# LEDCube.net
KiCad netlist of a schematic drawn in EAGLE
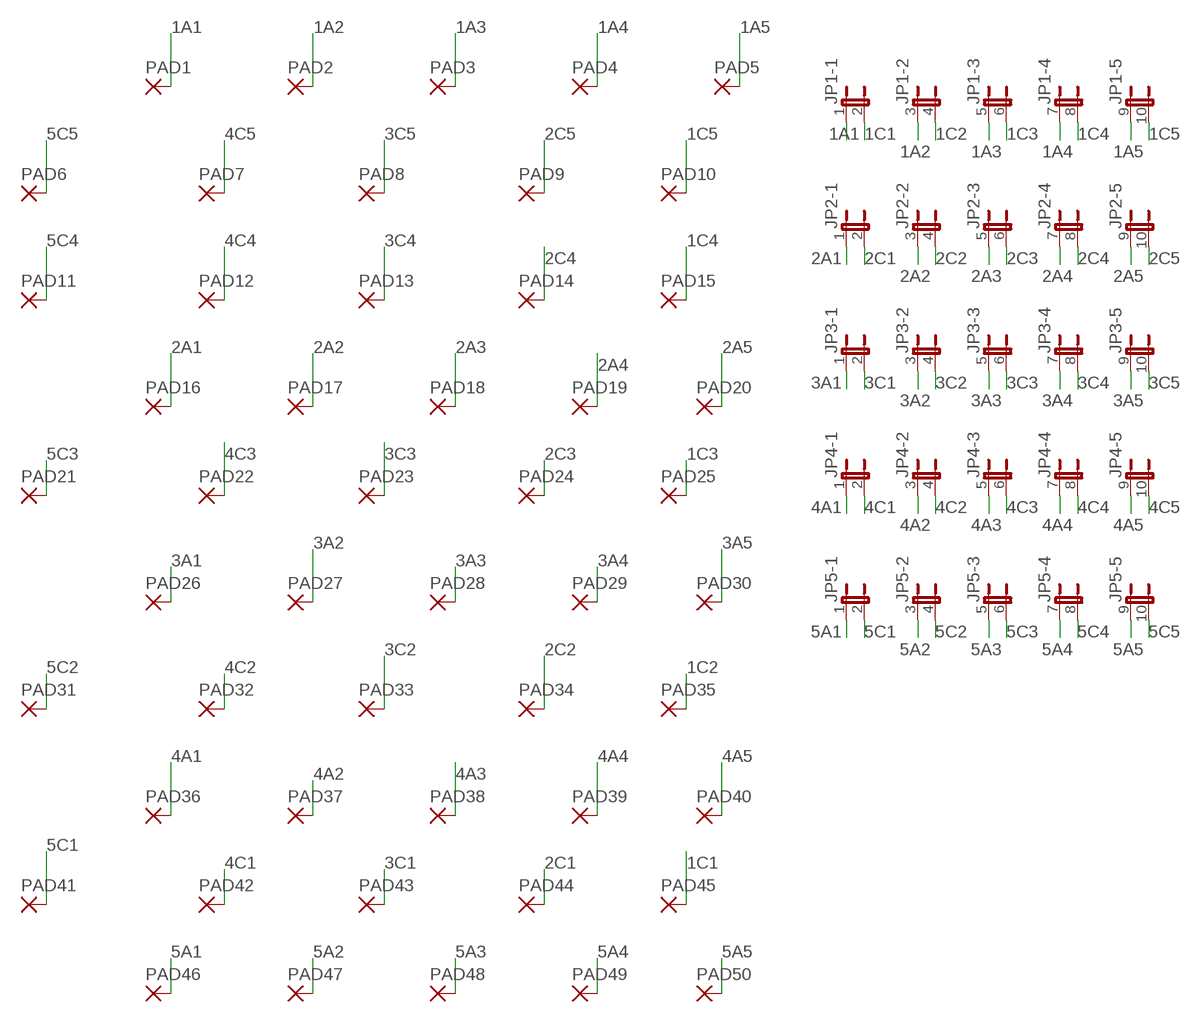
[diagram p0: schematic, sheet 1]

(export (version "E")
  (design (tool "Eeschema 10.0.6"))
  (components
    (comp (ref "JP1")
      (value "JP5QE")
      (footprint "eagle-import:JP5Q")
      (libsource (lib "eagle-import") (part "JP5QE"))
    )
    (comp (ref "JP2")
      (value "JP5QE")
      (footprint "eagle-import:JP5Q")
      (libsource (lib "eagle-import") (part "JP5QE"))
    )
    (comp (ref "JP3")
      (value "JP5QE")
      (footprint "eagle-import:JP5Q")
      (libsource (lib "eagle-import") (part "JP5QE"))
    )
    (comp (ref "JP4")
      (value "JP5QE")
      (footprint "eagle-import:JP5Q")
      (libsource (lib "eagle-import") (part "JP5QE"))
    )
    (comp (ref "JP5")
      (value "JP5QE")
      (footprint "eagle-import:JP5Q")
      (libsource (lib "eagle-import") (part "JP5QE"))
    )
    (comp (ref "PAD1")
      (value "2,54/1,1")
      (footprint "eagle-import:2,54_1,1")
      (libsource (lib "eagle-import") (part "2,54/1,1"))
    )
    (comp (ref "PAD2")
      (value "2,54/1,1")
      (footprint "eagle-import:2,54_1,1")
      (libsource (lib "eagle-import") (part "2,54/1,1"))
    )
    (comp (ref "PAD3")
      (value "2,54/1,1")
      (footprint "eagle-import:2,54_1,1")
      (libsource (lib "eagle-import") (part "2,54/1,1"))
    )
    (comp (ref "PAD4")
      (value "2,54/1,1")
      (footprint "eagle-import:2,54_1,1")
      (libsource (lib "eagle-import") (part "2,54/1,1"))
    )
    (comp (ref "PAD5")
      (value "2,54/1,1")
      (footprint "eagle-import:2,54_1,1")
      (libsource (lib "eagle-import") (part "2,54/1,1"))
    )
    (comp (ref "PAD6")
      (value "2,54/1,1")
      (footprint "eagle-import:2,54_1,1")
      (libsource (lib "eagle-import") (part "2,54/1,1"))
    )
    (comp (ref "PAD7")
      (value "2,54/1,1")
      (footprint "eagle-import:2,54_1,1")
      (libsource (lib "eagle-import") (part "2,54/1,1"))
    )
    (comp (ref "PAD8")
      (value "2,54/1,1")
      (footprint "eagle-import:2,54_1,1")
      (libsource (lib "eagle-import") (part "2,54/1,1"))
    )
    (comp (ref "PAD9")
      (value "2,54/1,1")
      (footprint "eagle-import:2,54_1,1")
      (libsource (lib "eagle-import") (part "2,54/1,1"))
    )
    (comp (ref "PAD10")
      (value "2,54/1,1")
      (footprint "eagle-import:2,54_1,1")
      (libsource (lib "eagle-import") (part "2,54/1,1"))
    )
    (comp (ref "PAD11")
      (value "2,54/1,1")
      (footprint "eagle-import:2,54_1,1")
      (libsource (lib "eagle-import") (part "2,54/1,1"))
    )
    (comp (ref "PAD12")
      (value "2,54/1,1")
      (footprint "eagle-import:2,54_1,1")
      (libsource (lib "eagle-import") (part "2,54/1,1"))
    )
    (comp (ref "PAD13")
      (value "2,54/1,1")
      (footprint "eagle-import:2,54_1,1")
      (libsource (lib "eagle-import") (part "2,54/1,1"))
    )
    (comp (ref "PAD14")
      (value "2,54/1,1")
      (footprint "eagle-import:2,54_1,1")
      (libsource (lib "eagle-import") (part "2,54/1,1"))
    )
    (comp (ref "PAD15")
      (value "2,54/1,1")
      (footprint "eagle-import:2,54_1,1")
      (libsource (lib "eagle-import") (part "2,54/1,1"))
    )
    (comp (ref "PAD16")
      (value "2,54/1,1")
      (footprint "eagle-import:2,54_1,1")
      (libsource (lib "eagle-import") (part "2,54/1,1"))
    )
    (comp (ref "PAD17")
      (value "2,54/1,1")
      (footprint "eagle-import:2,54_1,1")
      (libsource (lib "eagle-import") (part "2,54/1,1"))
    )
    (comp (ref "PAD18")
      (value "2,54/1,1")
      (footprint "eagle-import:2,54_1,1")
      (libsource (lib "eagle-import") (part "2,54/1,1"))
    )
    (comp (ref "PAD19")
      (value "2,54/1,1")
      (footprint "eagle-import:2,54_1,1")
      (libsource (lib "eagle-import") (part "2,54/1,1"))
    )
    (comp (ref "PAD20")
      (value "2,54/1,1")
      (footprint "eagle-import:2,54_1,1")
      (libsource (lib "eagle-import") (part "2,54/1,1"))
    )
    (comp (ref "PAD21")
      (value "2,54/1,1")
      (footprint "eagle-import:2,54_1,1")
      (libsource (lib "eagle-import") (part "2,54/1,1"))
    )
    (comp (ref "PAD22")
      (value "2,54/1,1")
      (footprint "eagle-import:2,54_1,1")
      (libsource (lib "eagle-import") (part "2,54/1,1"))
    )
    (comp (ref "PAD23")
      (value "2,54/1,1")
      (footprint "eagle-import:2,54_1,1")
      (libsource (lib "eagle-import") (part "2,54/1,1"))
    )
    (comp (ref "PAD24")
      (value "2,54/1,1")
      (footprint "eagle-import:2,54_1,1")
      (libsource (lib "eagle-import") (part "2,54/1,1"))
    )
    (comp (ref "PAD25")
      (value "2,54/1,1")
      (footprint "eagle-import:2,54_1,1")
      (libsource (lib "eagle-import") (part "2,54/1,1"))
    )
    (comp (ref "PAD26")
      (value "2,54/1,1")
      (footprint "eagle-import:2,54_1,1")
      (libsource (lib "eagle-import") (part "2,54/1,1"))
    )
    (comp (ref "PAD27")
      (value "2,54/1,1")
      (footprint "eagle-import:2,54_1,1")
      (libsource (lib "eagle-import") (part "2,54/1,1"))
    )
    (comp (ref "PAD28")
      (value "2,54/1,1")
      (footprint "eagle-import:2,54_1,1")
      (libsource (lib "eagle-import") (part "2,54/1,1"))
    )
    (comp (ref "PAD29")
      (value "2,54/1,1")
      (footprint "eagle-import:2,54_1,1")
      (libsource (lib "eagle-import") (part "2,54/1,1"))
    )
    (comp (ref "PAD30")
      (value "2,54/1,1")
      (footprint "eagle-import:2,54_1,1")
      (libsource (lib "eagle-import") (part "2,54/1,1"))
    )
    (comp (ref "PAD31")
      (value "2,54/1,1")
      (footprint "eagle-import:2,54_1,1")
      (libsource (lib "eagle-import") (part "2,54/1,1"))
    )
    (comp (ref "PAD32")
      (value "2,54/1,1")
      (footprint "eagle-import:2,54_1,1")
      (libsource (lib "eagle-import") (part "2,54/1,1"))
    )
    (comp (ref "PAD33")
      (value "2,54/1,1")
      (footprint "eagle-import:2,54_1,1")
      (libsource (lib "eagle-import") (part "2,54/1,1"))
    )
    (comp (ref "PAD34")
      (value "2,54/1,1")
      (footprint "eagle-import:2,54_1,1")
      (libsource (lib "eagle-import") (part "2,54/1,1"))
    )
    (comp (ref "PAD35")
      (value "2,54/1,1")
      (footprint "eagle-import:2,54_1,1")
      (libsource (lib "eagle-import") (part "2,54/1,1"))
    )
    (comp (ref "PAD36")
      (value "2,54/1,1")
      (footprint "eagle-import:2,54_1,1")
      (libsource (lib "eagle-import") (part "2,54/1,1"))
    )
    (comp (ref "PAD37")
      (value "2,54/1,1")
      (footprint "eagle-import:2,54_1,1")
      (libsource (lib "eagle-import") (part "2,54/1,1"))
    )
    (comp (ref "PAD38")
      (value "2,54/1,1")
      (footprint "eagle-import:2,54_1,1")
      (libsource (lib "eagle-import") (part "2,54/1,1"))
    )
    (comp (ref "PAD39")
      (value "2,54/1,1")
      (footprint "eagle-import:2,54_1,1")
      (libsource (lib "eagle-import") (part "2,54/1,1"))
    )
    (comp (ref "PAD40")
      (value "2,54/1,1")
      (footprint "eagle-import:2,54_1,1")
      (libsource (lib "eagle-import") (part "2,54/1,1"))
    )
    (comp (ref "PAD41")
      (value "2,54/1,1")
      (footprint "eagle-import:2,54_1,1")
      (libsource (lib "eagle-import") (part "2,54/1,1"))
    )
    (comp (ref "PAD42")
      (value "2,54/1,1")
      (footprint "eagle-import:2,54_1,1")
      (libsource (lib "eagle-import") (part "2,54/1,1"))
    )
    (comp (ref "PAD43")
      (value "2,54/1,1")
      (footprint "eagle-import:2,54_1,1")
      (libsource (lib "eagle-import") (part "2,54/1,1"))
    )
    (comp (ref "PAD44")
      (value "2,54/1,1")
      (footprint "eagle-import:2,54_1,1")
      (libsource (lib "eagle-import") (part "2,54/1,1"))
    )
    (comp (ref "PAD45")
      (value "2,54/1,1")
      (footprint "eagle-import:2,54_1,1")
      (libsource (lib "eagle-import") (part "2,54/1,1"))
    )
    (comp (ref "PAD46")
      (value "2,54/1,1")
      (footprint "eagle-import:2,54_1,1")
      (libsource (lib "eagle-import") (part "2,54/1,1"))
    )
    (comp (ref "PAD47")
      (value "2,54/1,1")
      (footprint "eagle-import:2,54_1,1")
      (libsource (lib "eagle-import") (part "2,54/1,1"))
    )
    (comp (ref "PAD48")
      (value "2,54/1,1")
      (footprint "eagle-import:2,54_1,1")
      (libsource (lib "eagle-import") (part "2,54/1,1"))
    )
    (comp (ref "PAD49")
      (value "2,54/1,1")
      (footprint "eagle-import:2,54_1,1")
      (libsource (lib "eagle-import") (part "2,54/1,1"))
    )
    (comp (ref "PAD50")
      (value "2,54/1,1")
      (footprint "eagle-import:2,54_1,1")
      (libsource (lib "eagle-import") (part "2,54/1,1"))
    )
  )
  (nets
    (net (code "1") (name "/1A1") (class "Default")
      (node (ref "JP1") (pin "1") (pinfunction "1_1") (pintype "passive"))
      (node (ref "PAD1") (pin "1") (pinfunction "P_1") (pintype "passive"))
    )
    (net (code "2") (name "/1A2") (class "Default")
      (node (ref "JP1") (pin "3") (pinfunction "1_3") (pintype "passive"))
      (node (ref "PAD2") (pin "1") (pinfunction "P_1") (pintype "passive"))
    )
    (net (code "3") (name "/1A3") (class "Default")
      (node (ref "JP1") (pin "5") (pinfunction "1_5") (pintype "passive"))
      (node (ref "PAD3") (pin "1") (pinfunction "P_1") (pintype "passive"))
    )
    (net (code "4") (name "/1A4") (class "Default")
      (node (ref "JP1") (pin "7") (pinfunction "1_7") (pintype "passive"))
      (node (ref "PAD4") (pin "1") (pinfunction "P_1") (pintype "passive"))
    )
    (net (code "5") (name "/1A5") (class "Default")
      (node (ref "JP1") (pin "9") (pinfunction "1_9") (pintype "passive"))
      (node (ref "PAD5") (pin "1") (pinfunction "P_1") (pintype "passive"))
    )
    (net (code "6") (name "/1C1") (class "Default")
      (node (ref "JP1") (pin "2") (pinfunction "2_2") (pintype "passive"))
      (node (ref "PAD45") (pin "1") (pinfunction "P_1") (pintype "passive"))
    )
    (net (code "7") (name "/1C2") (class "Default")
      (node (ref "JP1") (pin "4") (pinfunction "2_4") (pintype "passive"))
      (node (ref "PAD35") (pin "1") (pinfunction "P_1") (pintype "passive"))
    )
    (net (code "8") (name "/1C3") (class "Default")
      (node (ref "JP1") (pin "6") (pinfunction "2_6") (pintype "passive"))
      (node (ref "PAD25") (pin "1") (pinfunction "P_1") (pintype "passive"))
    )
    (net (code "9") (name "/1C4") (class "Default")
      (node (ref "JP1") (pin "8") (pinfunction "2_8") (pintype "passive"))
      (node (ref "PAD15") (pin "1") (pinfunction "P_1") (pintype "passive"))
    )
    (net (code "10") (name "/1C5") (class "Default")
      (node (ref "JP1") (pin "10") (pinfunction "2_10") (pintype "passive"))
      (node (ref "PAD10") (pin "1") (pinfunction "P_1") (pintype "passive"))
    )
    (net (code "11") (name "/2A1") (class "Default")
      (node (ref "JP2") (pin "1") (pinfunction "1_1") (pintype "passive"))
      (node (ref "PAD16") (pin "1") (pinfunction "P_1") (pintype "passive"))
    )
    (net (code "12") (name "/2A2") (class "Default")
      (node (ref "JP2") (pin "3") (pinfunction "1_3") (pintype "passive"))
      (node (ref "PAD17") (pin "1") (pinfunction "P_1") (pintype "passive"))
    )
    (net (code "13") (name "/2A3") (class "Default")
      (node (ref "JP2") (pin "5") (pinfunction "1_5") (pintype "passive"))
      (node (ref "PAD18") (pin "1") (pinfunction "P_1") (pintype "passive"))
    )
    (net (code "14") (name "/2A4") (class "Default")
      (node (ref "JP2") (pin "7") (pinfunction "1_7") (pintype "passive"))
      (node (ref "PAD19") (pin "1") (pinfunction "P_1") (pintype "passive"))
    )
    (net (code "15") (name "/2A5") (class "Default")
      (node (ref "JP2") (pin "9") (pinfunction "1_9") (pintype "passive"))
      (node (ref "PAD20") (pin "1") (pinfunction "P_1") (pintype "passive"))
    )
    (net (code "16") (name "/2C1") (class "Default")
      (node (ref "JP2") (pin "2") (pinfunction "2_2") (pintype "passive"))
      (node (ref "PAD44") (pin "1") (pinfunction "P_1") (pintype "passive"))
    )
    (net (code "17") (name "/2C2") (class "Default")
      (node (ref "JP2") (pin "4") (pinfunction "2_4") (pintype "passive"))
      (node (ref "PAD34") (pin "1") (pinfunction "P_1") (pintype "passive"))
    )
    (net (code "18") (name "/2C3") (class "Default")
      (node (ref "JP2") (pin "6") (pinfunction "2_6") (pintype "passive"))
      (node (ref "PAD24") (pin "1") (pinfunction "P_1") (pintype "passive"))
    )
    (net (code "19") (name "/2C4") (class "Default")
      (node (ref "JP2") (pin "8") (pinfunction "2_8") (pintype "passive"))
      (node (ref "PAD14") (pin "1") (pinfunction "P_1") (pintype "passive"))
    )
    (net (code "20") (name "/2C5") (class "Default")
      (node (ref "JP2") (pin "10") (pinfunction "2_10") (pintype "passive"))
      (node (ref "PAD9") (pin "1") (pinfunction "P_1") (pintype "passive"))
    )
    (net (code "21") (name "/3A1") (class "Default")
      (node (ref "JP3") (pin "1") (pinfunction "1_1") (pintype "passive"))
      (node (ref "PAD26") (pin "1") (pinfunction "P_1") (pintype "passive"))
    )
    (net (code "22") (name "/3A2") (class "Default")
      (node (ref "JP3") (pin "3") (pinfunction "1_3") (pintype "passive"))
      (node (ref "PAD27") (pin "1") (pinfunction "P_1") (pintype "passive"))
    )
    (net (code "23") (name "/3A3") (class "Default")
      (node (ref "JP3") (pin "5") (pinfunction "1_5") (pintype "passive"))
      (node (ref "PAD28") (pin "1") (pinfunction "P_1") (pintype "passive"))
    )
    (net (code "24") (name "/3A4") (class "Default")
      (node (ref "JP3") (pin "7") (pinfunction "1_7") (pintype "passive"))
      (node (ref "PAD29") (pin "1") (pinfunction "P_1") (pintype "passive"))
    )
    (net (code "25") (name "/3A5") (class "Default")
      (node (ref "JP3") (pin "9") (pinfunction "1_9") (pintype "passive"))
      (node (ref "PAD30") (pin "1") (pinfunction "P_1") (pintype "passive"))
    )
    (net (code "26") (name "/3C1") (class "Default")
      (node (ref "JP3") (pin "2") (pinfunction "2_2") (pintype "passive"))
      (node (ref "PAD43") (pin "1") (pinfunction "P_1") (pintype "passive"))
    )
    (net (code "27") (name "/3C2") (class "Default")
      (node (ref "JP3") (pin "4") (pinfunction "2_4") (pintype "passive"))
      (node (ref "PAD33") (pin "1") (pinfunction "P_1") (pintype "passive"))
    )
    (net (code "28") (name "/3C3") (class "Default")
      (node (ref "JP3") (pin "6") (pinfunction "2_6") (pintype "passive"))
      (node (ref "PAD23") (pin "1") (pinfunction "P_1") (pintype "passive"))
    )
    (net (code "29") (name "/3C4") (class "Default")
      (node (ref "JP3") (pin "8") (pinfunction "2_8") (pintype "passive"))
      (node (ref "PAD13") (pin "1") (pinfunction "P_1") (pintype "passive"))
    )
    (net (code "30") (name "/3C5") (class "Default")
      (node (ref "JP3") (pin "10") (pinfunction "2_10") (pintype "passive"))
      (node (ref "PAD8") (pin "1") (pinfunction "P_1") (pintype "passive"))
    )
    (net (code "31") (name "/4A1") (class "Default")
      (node (ref "JP4") (pin "1") (pinfunction "1_1") (pintype "passive"))
      (node (ref "PAD36") (pin "1") (pinfunction "P_1") (pintype "passive"))
    )
    (net (code "32") (name "/4A2") (class "Default")
      (node (ref "JP4") (pin "3") (pinfunction "1_3") (pintype "passive"))
      (node (ref "PAD37") (pin "1") (pinfunction "P_1") (pintype "passive"))
    )
    (net (code "33") (name "/4A3") (class "Default")
      (node (ref "JP4") (pin "5") (pinfunction "1_5") (pintype "passive"))
      (node (ref "PAD38") (pin "1") (pinfunction "P_1") (pintype "passive"))
    )
    (net (code "34") (name "/4A4") (class "Default")
      (node (ref "JP4") (pin "7") (pinfunction "1_7") (pintype "passive"))
      (node (ref "PAD39") (pin "1") (pinfunction "P_1") (pintype "passive"))
    )
    (net (code "35") (name "/4A5") (class "Default")
      (node (ref "JP4") (pin "9") (pinfunction "1_9") (pintype "passive"))
      (node (ref "PAD40") (pin "1") (pinfunction "P_1") (pintype "passive"))
    )
    (net (code "36") (name "/4C1") (class "Default")
      (node (ref "JP4") (pin "2") (pinfunction "2_2") (pintype "passive"))
      (node (ref "PAD42") (pin "1") (pinfunction "P_1") (pintype "passive"))
    )
    (net (code "37") (name "/4C2") (class "Default")
      (node (ref "JP4") (pin "4") (pinfunction "2_4") (pintype "passive"))
      (node (ref "PAD32") (pin "1") (pinfunction "P_1") (pintype "passive"))
    )
    (net (code "38") (name "/4C3") (class "Default")
      (node (ref "JP4") (pin "6") (pinfunction "2_6") (pintype "passive"))
      (node (ref "PAD22") (pin "1") (pinfunction "P_1") (pintype "passive"))
    )
    (net (code "39") (name "/4C4") (class "Default")
      (node (ref "JP4") (pin "8") (pinfunction "2_8") (pintype "passive"))
      (node (ref "PAD12") (pin "1") (pinfunction "P_1") (pintype "passive"))
    )
    (net (code "40") (name "/4C5") (class "Default")
      (node (ref "JP4") (pin "10") (pinfunction "2_10") (pintype "passive"))
      (node (ref "PAD7") (pin "1") (pinfunction "P_1") (pintype "passive"))
    )
    (net (code "41") (name "/5A1") (class "Default")
      (node (ref "JP5") (pin "1") (pinfunction "1_1") (pintype "passive"))
      (node (ref "PAD46") (pin "1") (pinfunction "P_1") (pintype "passive"))
    )
    (net (code "42") (name "/5A2") (class "Default")
      (node (ref "JP5") (pin "3") (pinfunction "1_3") (pintype "passive"))
      (node (ref "PAD47") (pin "1") (pinfunction "P_1") (pintype "passive"))
    )
    (net (code "43") (name "/5A3") (class "Default")
      (node (ref "JP5") (pin "5") (pinfunction "1_5") (pintype "passive"))
      (node (ref "PAD48") (pin "1") (pinfunction "P_1") (pintype "passive"))
    )
    (net (code "44") (name "/5A4") (class "Default")
      (node (ref "JP5") (pin "7") (pinfunction "1_7") (pintype "passive"))
      (node (ref "PAD49") (pin "1") (pinfunction "P_1") (pintype "passive"))
    )
    (net (code "45") (name "/5A5") (class "Default")
      (node (ref "JP5") (pin "9") (pinfunction "1_9") (pintype "passive"))
      (node (ref "PAD50") (pin "1") (pinfunction "P_1") (pintype "passive"))
    )
    (net (code "46") (name "/5C1") (class "Default")
      (node (ref "JP5") (pin "2") (pinfunction "2_2") (pintype "passive"))
      (node (ref "PAD41") (pin "1") (pinfunction "P_1") (pintype "passive"))
    )
    (net (code "47") (name "/5C2") (class "Default")
      (node (ref "JP5") (pin "4") (pinfunction "2_4") (pintype "passive"))
      (node (ref "PAD31") (pin "1") (pinfunction "P_1") (pintype "passive"))
    )
    (net (code "48") (name "/5C3") (class "Default")
      (node (ref "JP5") (pin "6") (pinfunction "2_6") (pintype "passive"))
      (node (ref "PAD21") (pin "1") (pinfunction "P_1") (pintype "passive"))
    )
    (net (code "49") (name "/5C4") (class "Default")
      (node (ref "JP5") (pin "8") (pinfunction "2_8") (pintype "passive"))
      (node (ref "PAD11") (pin "1") (pinfunction "P_1") (pintype "passive"))
    )
    (net (code "50") (name "/5C5") (class "Default")
      (node (ref "JP5") (pin "10") (pinfunction "2_10") (pintype "passive"))
      (node (ref "PAD6") (pin "1") (pinfunction "P_1") (pintype "passive"))
    )
  )
)
